# TOF-SCH.net
KiCad netlist of a schematic drawn in Altium Designer
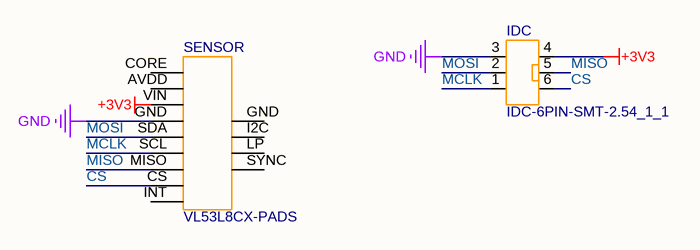
[diagram p0: TOF-SCH.SchDoc]

(export (version "E")
  (design (tool "Eeschema 10.0.6"))
  (components
    (comp (ref "IDC")
      (value "IDC-6PIN-SMT-2.54_1_1")
      (footprint "IDC-6PIN-SMT-2.54")
      (libsource (lib "RC") (part "IDC-6PIN-SMT-2.54_1_1"))
    )
    (comp (ref "SENSOR")
      (value "VL53L8CX-PADS")
      (footprint "VL53L8CX-PADS")
      (libsource (lib "RC") (part "VL53L8CX-PADS"))
    )
  )
  (nets
    (net (code "1") (name "+3V3") (class "Default")
      (node (ref "IDC") (pin "4") (pintype "passive"))
      (node (ref "SENSOR") (pin "VIN") (pinfunction "06_VIN") (pintype "passive"))
    )
    (net (code "2") (name "/CS") (class "Default")
      (node (ref "IDC") (pin "6") (pintype "passive"))
      (node (ref "SENSOR") (pin "CS") (pinfunction "02_CS") (pintype "passive"))
    )
    (net (code "3") (name "/MCLK") (class "Default")
      (node (ref "IDC") (pin "1") (pintype "passive"))
      (node (ref "SENSOR") (pin "SCL") (pinfunction "04_SCL") (pintype "passive"))
    )
    (net (code "4") (name "/MISO") (class "Default")
      (node (ref "IDC") (pin "5") (pintype "passive"))
      (node (ref "SENSOR") (pin "MISO") (pinfunction "03_MISO") (pintype "passive"))
    )
    (net (code "5") (name "/MOSI") (class "Default")
      (node (ref "IDC") (pin "2") (pintype "passive"))
      (node (ref "SENSOR") (pin "SDA") (pinfunction "05_SDA") (pintype "passive"))
    )
    (net (code "6") (name "GND") (class "Default")
      (node (ref "IDC") (pin "3") (pintype "passive"))
      (node (ref "SENSOR") (pin "GND") (pinfunction "06_GND") (pintype "passive"))
    )
    (net (code "7") (name "unconnected-(SENSOR-01-PadINT)") (class "Default")
      (node (ref "SENSOR") (pin "INT") (pinfunction "01_INT") (pintype "passive"))
    )
    (net (code "8") (name "unconnected-(SENSOR-06-PadAVDD)") (class "Default")
      (node (ref "SENSOR") (pin "AVDD") (pinfunction "06_AVDD") (pintype "passive"))
    )
    (net (code "9") (name "unconnected-(SENSOR-06-PadCORE)") (class "Default")
      (node (ref "SENSOR") (pin "CORE") (pinfunction "06_CORE") (pintype "passive"))
    )
    (net (code "10") (name "unconnected-(SENSOR-06-PadGND)") (class "Default")
      (node (ref "SENSOR") (pin "GND") (pinfunction "06_GND") (pintype "passive"))
    )
    (net (code "11") (name "unconnected-(SENSOR-06-PadI2C)") (class "Default")
      (node (ref "SENSOR") (pin "I2C") (pinfunction "06_I2C") (pintype "passive"))
    )
    (net (code "12") (name "unconnected-(SENSOR-06-PadLP)") (class "Default")
      (node (ref "SENSOR") (pin "LP") (pinfunction "06_LP") (pintype "passive"))
    )
    (net (code "13") (name "unconnected-(SENSOR-06-PadSYNC)") (class "Default")
      (node (ref "SENSOR") (pin "SYNC") (pinfunction "06_SYNC") (pintype "passive"))
    )
  )
)
